# Buck_12V.net
KiCad netlist of a schematic drawn in Altium Designer
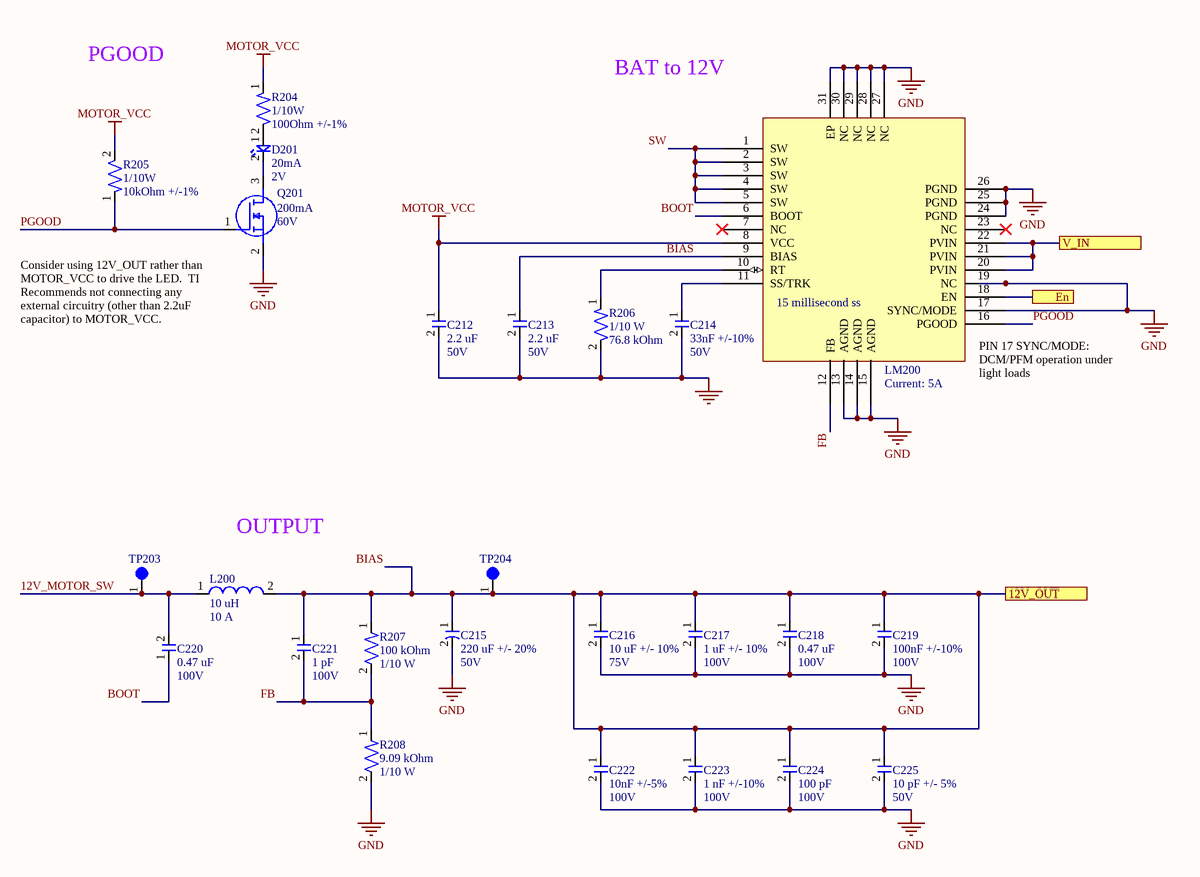
[diagram p0: Buck_12V.SchDoc]

(export (version "E")
  (design (tool "Eeschema 10.0.6"))
  (components
    (comp (ref "C212")
      (value "UMK107BBJ225KA-T")
      (footprint "CAP-0603")
      (description "2.2 µF ±10% 50V Ceramic Capacitor X5R 0603 (1608 Metric)")
      (fields (field (name "CAPACITANCE") "2.2 uF") (field (name "OLTAGE") "50V"))
      (libsource (lib "MasterLib") (part "CAP-2.2U-0001"))
    )
    (comp (ref "C213")
      (value "UMK107BBJ225KA-T")
      (footprint "CAP-0603")
      (description "2.2 µF ±10% 50V Ceramic Capacitor X5R 0603 (1608 Metric)")
      (fields (field (name "CAPACITANCE") "2.2 uF") (field (name "OLTAGE") "50V"))
      (libsource (lib "MasterLib") (part "CAP-2.2U-0001"))
    )
    (comp (ref "C214")
      (value "CC0603KRX7R9BB333")
      (footprint "CAP-0603")
      (description "0.033 µF ±10% 50V Ceramic Capacitor X7R 0603 (1608 Metric)")
      (fields
        (field (name "MANUFACTURER") "YAGEO")
        (field (name "CAPACITANCE") "33nF +/-10%")
        (field (name "VOLTAGE RATING") "50V")
      )
      (libsource (lib "MasterLib") (part "CAP-33N-0001"))
    )
    (comp (ref "C215")
      (value "50TZV220M10X10.5")
      (footprint "ELEC-220U-0003")
      (description "220 µF 50 V Aluminum Electrolytic Capacitors Radial, Can - SMD 2000 Hrs @ 105°C")
      (fields (field (name "CAPACITANCE") "220 uF +/- 20%") (field (name "VOLTAGE RATING") "50V"))
      (libsource (lib "MasterLib") (part "ELEC-220U-0003"))
    )
    (comp (ref "C216")
      (value "C3225X7R1N106K250AC")
      (footprint "CAP-1210")
      (description "10 µF ±10% 75V Ceramic Capacitor X7R 1210 (3225 Metric)")
      (fields (field (name "CAPACITANCE") "10 uF +/- 10%") (field (name "VOLTAGE RATING") "75V"))
      (libsource (lib "MasterLib") (part "CAP-10U-0004"))
    )
    (comp (ref "C217")
      (value "CL31B105KCHNNNE")
      (footprint "CAP-1206 - duplicate")
      (description "1 µF ±10% 100V Ceramic Capacitor X7R 1206 (3216 Metric)")
      (fields (field (name "CAPACITANCE") "1 uF +/- 10%") (field (name "VOLTAGE") "100V"))
      (libsource (lib "MasterLib") (part "CAP-1U-0001"))
    )
    (comp (ref "C218")
      (value "KAM21KR72A474KL")
      (footprint "CAP-0805")
      (description "0.47 µF ±10% 100V Ceramic Capacitor X7R 0805 (2012 Metric)")
      (fields
        (field (name "TOLERANCE") "+/- 10%")
        (field (name "CAPACITANCE") "0.47 uF")
        (field (name "VOLTAGE") "100V")
      )
      (libsource (lib "MasterLib") (part "CAP-0.47U-0001"))
    )
    (comp (ref "C219")
      (value "CC0603KRX7R0BB104")
      (footprint "CAP-0603")
      (description "CAP CER 0.1UF 100V X7R 0603")
      (fields
        (field (name "MANUFACTURER") "YAGEO")
        (field (name "CAPACITANCE") "100nF +/-10%")
        (field (name "VOLTAGE RATING") "100V")
      )
      (libsource (lib "MasterLib") (part "CAP-100N-0001"))
    )
    (comp (ref "C220")
      (value "KAM21KR72A474KL")
      (footprint "CAP-0805")
      (description "0.47 µF ±10% 100V Ceramic Capacitor X7R 0805 (2012 Metric)")
      (fields
        (field (name "TOLERANCE") "+/- 10%")
        (field (name "CAPACITANCE") "0.47 uF")
        (field (name "VOLTAGE") "100V")
      )
      (libsource (lib "MasterLib") (part "CAP-0.47U-0001"))
    )
    (comp (ref "C221")
      (value "885012006087")
      (footprint "CAP-0603")
      (description "1 pF ±0.25pF 100V Ceramic Capacitor C0G, NP0 0603 (1608 Metric)")
      (fields
        (field (name "TOLERANCE") "+/- 0.25 pF")
        (field (name "CAPACITANCE") "1 pF")
        (field (name "VOLTAGE") "100V")
      )
      (libsource (lib "MasterLib") (part "CAP-1P-0001"))
    )
    (comp (ref "C222")
      (value "C1608C0G2A103J080AC")
      (footprint "CAP-0603")
      (description "CAP CER 10000PF 100V C0G 0603")
      (fields
        (field (name "MANUFACTURER") "TDK Corporation")
        (field (name "CAPACITANCE") "10nF +/-5%")
        (field (name "VOLTAGE RATING") "100V")
      )
      (libsource (lib "MasterLib") (part "CAP-10N-0002"))
    )
    (comp (ref "C223")
      (value "C0603Y102K1RAC7867")
      (footprint "CAP-0603")
      (description "1000 pF ±10% 100V Ceramic Capacitor X7R 0603 (1608 Metric)")
      (fields (field (name "CAPACITANCE") "1 nF +/-10%") (field (name "VOLTAGE") "100V"))
      (libsource (lib "MasterLib") (part "CAP-1N-0001"))
    )
    (comp (ref "C224")
      (value "0603N101J101CT")
      (footprint "CAP-0603")
      (description "100 pF ±5% 100V Ceramic Capacitor C0G, NP0 0603 (1608 Metric)")
      (fields
        (field (name "TOLERANCE") "+/-5%")
        (field (name "CAPACITANCE") "100 pF")
        (field (name "VOLTAGE") "100V")
      )
      (libsource (lib "MasterLib") (part "CAP-100P-0002"))
    )
    (comp (ref "C225")
      (value "0603N100J500CT")
      (footprint "CAP-0603")
      (description "10 pF ±5% 50V Ceramic Capacitor C0G, NP0 0603 (1608 Metric)")
      (fields
        (field (name "MANUFACTURER") "Walshin Technology Corporation")
        (field (name "CAPACITANCE") "10 pF +/- 5%")
        (field (name "VOLTAGE RATING") "50V")
      )
      (libsource (lib "MasterLib") (part "CAP-10P-0001"))
    )
    (comp (ref "D201")
      (value "150060AS75000")
      (footprint "LED-0603")
      (description "CAP CER 0.1UF 100V X7R 0603")
      (fields
        (field (name "MANUFACTURER") "Wurth Electronik")
        (field (name "CURRENT RATING") "20mA")
        (field (name "VF") "2V")
      )
      (libsource (lib "MasterLib") (part "LED_Amber_0001"))
    )
    (comp (ref "L200")
      (value "SRP1270-100M")
      (footprint "PWRIND-10U-0002")
      (description "10 µH Shielded Drum Core, Wirewound Inductor 10 A 16.8mOhm Max Nonstandard")
      (fields
        (field (name "TOLERANCE") "+/- 20%")
        (field (name "INDUCTANCE") "10 uH")
        (field (name "DCI") "10 A")
      )
      (libsource (lib "MasterLib") (part "PWRIND-10U-0002"))
    )
    (comp (ref "LM200")
      (value "LM76005RNPR")
      (footprint "IC-30-WQFN(6x4)")
      (description "Buck Switching Regulator IC Positive Adjustable 1V 1 Output 5A 30-WFQFN Exposed Pad")
      (fields (field (name "MANUFACTURER") "Texas Instruments") (field (name "CURRENT") "5A"))
      (libsource (lib "MasterLib") (part "IC-BUCK-0006"))
    )
    (comp (ref "Q201")
      (value "T2N7002AK,LM")
      (footprint "NMOS-SOT23-3")
      (description "MOSFET N-CH 60V 200MA SOT23")
      (fields
        (field (name "MANUFACTURER") "Toshiba")
        (field (name "ID-CONTINUOUS") "200mA")
        (field (name "VDS-MAX") "60V")
      )
      (libsource (lib "MasterLib") (part "NMOS-200MA-0001"))
    )
    (comp (ref "R204")
      (value "AC0603FR-10100RL")
      (footprint "RES-0603")
      (description "100 Ohms ±1% 0.1W, 1/10W Chip Resistor 0603 (1608 Metric) Automotive AEC-Q200 Thick Film")
      (fields
        (field (name "MANUFACTURER") "YAGEO")
        (field (name "POWER RATING") "1/10W")
        (field (name "RESISTANCE") "100Ohm +/-1%")
      )
      (libsource (lib "MasterLib") (part "RES-100-0002"))
    )
    (comp (ref "R205")
      (value "RC0603FR-0710KP")
      (footprint "RES-0603")
      (description "RES SMD 10K OHM 1% 1/10W 0603")
      (fields
        (field (name "MANUFACTURER") "YAGEO")
        (field (name "POWER RATING") "1/10W")
        (field (name "RESISTANCE") "10kOhm +/-1%")
      )
      (libsource (lib "MasterLib") (part "RES-10K-0002"))
    )
    (comp (ref "R206")
      (value "RC0603FR-0776K8L")
      (footprint "RES-0603")
      (description "76.8 kOhms ±1% 0.1W, 1/10W Chip Resistor 0603 (1608 Metric) Moisture Resistant Thick Film")
      (fields
        (field (name "MANUFACTURER") "Yageo")
        (field (name "TOLERANCE") "+/- 1%")
        (field (name "POWER") "1/10 W")
        (field (name "RESISTANCE") "76.8 kOhm")
      )
      (libsource (lib "MasterLib") (part "RES-76.8K-0001"))
    )
    (comp (ref "R207")
      (value "RC0603FR-07100KL")
      (footprint "RES-0603")
      (description "100 kOhms ±1% 0.1W, 1/10W Chip Resistor 0603 (1608 Metric) Moisture Resistant Thick Film")
      (fields
        (field (name "TOLERANCE") "+/- 1%")
        (field (name "RESISTANCE") "100 kOhm")
        (field (name "POWER") "1/10 W")
      )
      (libsource (lib "MasterLib") (part "RES-100K-0003"))
    )
    (comp (ref "R208")
      (value "RC0603FR-079K09L")
      (footprint "RES-0603")
      (description "9.09 kOhms ±1% 0.1W, 1/10W Chip Resistor 0603 (1608 Metric) Moisture Resistant Thick Film")
      (fields
        (field (name "TOLERANCE") "+/-1%")
        (field (name "RESISTANCE") "9.09 kOhm")
        (field (name "POWER") "1/10 W")
      )
      (libsource (lib "MasterLib") (part "RES-9.09K-0001"))
    )
    (comp (ref "TP203")
      (value "5003")
      (footprint "TEST-POINT-0001")
      (description "Oranange PC Test Point, Miniature Phoisphor Bronze Silver Plating Through Hole Mounting Type")
      (libsource (lib "MasterLib") (part "TEST-POINT-0001"))
    )
    (comp (ref "TP204")
      (value "5003")
      (footprint "TEST-POINT-0001")
      (description "Oranange PC Test Point, Miniature Phoisphor Bronze Silver Plating Through Hole Mounting Type")
      (libsource (lib "MasterLib") (part "TEST-POINT-0001"))
    )
  )
  (nets
    (net (code "1") (name "/12V_MOTOR_SW") (class "Default")
      (node (ref "C220") (pin "2") (pinfunction "2_2") (pintype "passive"))
      (node (ref "L200") (pin "1") (pinfunction "1_1") (pintype "passive"))
      (node (ref "TP203") (pin "1") (pinfunction "0_1") (pintype "passive"))
    )
    (net (code "2") (name "/BIAS") (class "Default")
      (node (ref "C213") (pin "1") (pinfunction "1_1") (pintype "passive"))
      (node (ref "C215") (pin "1") (pinfunction "1_1") (pintype "passive"))
      (node (ref "C216") (pin "1") (pinfunction "1_1") (pintype "passive"))
      (node (ref "C217") (pin "1") (pinfunction "1_1") (pintype "passive"))
      (node (ref "C218") (pin "1") (pinfunction "1_1") (pintype "passive"))
      (node (ref "C219") (pin "1") (pinfunction "1_1") (pintype "passive"))
      (node (ref "C221") (pin "1") (pinfunction "1_1") (pintype "passive"))
      (node (ref "C222") (pin "1") (pinfunction "1_1") (pintype "passive"))
      (node (ref "C223") (pin "1") (pinfunction "1_1") (pintype "passive"))
      (node (ref "C224") (pin "1") (pinfunction "1_1") (pintype "passive"))
      (node (ref "C225") (pin "1") (pinfunction "1_1") (pintype "passive"))
      (node (ref "L200") (pin "2") (pinfunction "2_2") (pintype "passive"))
      (node (ref "LM200") (pin "9") (pinfunction "BIAS_9") (pintype "power_in"))
      (node (ref "R207") (pin "1") (pinfunction "1_1") (pintype "passive"))
      (node (ref "TP204") (pin "1") (pinfunction "0_1") (pintype "passive"))
    )
    (net (code "3") (name "/BOOT") (class "Default")
      (node (ref "C220") (pin "1") (pinfunction "1_1") (pintype "passive"))
      (node (ref "LM200") (pin "6") (pinfunction "BOOT_6") (pintype "power_in"))
    )
    (net (code "4") (name "/En") (class "Default")
      (node (ref "LM200") (pin "18") (pinfunction "EN_18") (pintype "power_in"))
    )
    (net (code "5") (name "/FB") (class "Default")
      (node (ref "C221") (pin "2") (pinfunction "2_2") (pintype "passive"))
      (node (ref "LM200") (pin "12") (pinfunction "FB_12") (pintype "power_in"))
      (node (ref "R207") (pin "2") (pinfunction "2_2") (pintype "passive"))
      (node (ref "R208") (pin "1") (pinfunction "1_1") (pintype "passive"))
    )
    (net (code "6") (name "/PGOOD") (class "Default")
      (node (ref "LM200") (pin "16") (pinfunction "PGOOD_16") (pintype "power_in"))
      (node (ref "Q201") (pin "1") (pinfunction "G_1") (pintype "passive"))
      (node (ref "R205") (pin "1") (pinfunction "1_1") (pintype "passive"))
    )
    (net (code "7") (name "/SW") (class "Default")
      (node (ref "LM200") (pin "1") (pinfunction "SW_1") (pintype "power_in"))
      (node (ref "LM200") (pin "2") (pinfunction "SW_2") (pintype "power_in"))
      (node (ref "LM200") (pin "3") (pinfunction "SW_3") (pintype "power_in"))
      (node (ref "LM200") (pin "4") (pinfunction "SW_4") (pintype "power_in"))
      (node (ref "LM200") (pin "5") (pinfunction "SW_5") (pintype "power_in"))
    )
    (net (code "8") (name "/V_IN") (class "Default")
      (node (ref "LM200") (pin "20") (pinfunction "PVIN_20") (pintype "power_in"))
      (node (ref "LM200") (pin "21") (pinfunction "PVIN_21") (pintype "power_in"))
      (node (ref "LM200") (pin "22") (pinfunction "PVIN_22") (pintype "power_in"))
    )
    (net (code "9") (name "<NO NET>") (class "Default")
      (node (ref "C212") (pin "2") (pinfunction "2_2") (pintype "passive"))
      (node (ref "C213") (pin "2") (pinfunction "2_2") (pintype "passive"))
      (node (ref "C214") (pin "2") (pinfunction "2_2") (pintype "passive"))
      (node (ref "R206") (pin "2") (pinfunction "2_2") (pintype "passive"))
    )
    (net (code "10") (name "GND") (class "Default")
      (node (ref "C215") (pin "2") (pinfunction "2_2") (pintype "passive"))
      (node (ref "C216") (pin "2") (pinfunction "2_2") (pintype "passive"))
      (node (ref "C217") (pin "2") (pinfunction "2_2") (pintype "passive"))
      (node (ref "C218") (pin "2") (pinfunction "2_2") (pintype "passive"))
      (node (ref "C219") (pin "2") (pinfunction "2_2") (pintype "passive"))
      (node (ref "C222") (pin "2") (pinfunction "2_2") (pintype "passive"))
      (node (ref "C223") (pin "2") (pinfunction "2_2") (pintype "passive"))
      (node (ref "C224") (pin "2") (pinfunction "2_2") (pintype "passive"))
      (node (ref "C225") (pin "2") (pinfunction "2_2") (pintype "passive"))
      (node (ref "LM200") (pin "13") (pinfunction "AGND_13") (pintype "power_in"))
      (node (ref "LM200") (pin "14") (pinfunction "AGND_14") (pintype "power_in"))
      (node (ref "LM200") (pin "15") (pinfunction "AGND_15") (pintype "power_in"))
      (node (ref "LM200") (pin "17") (pinfunction "SYNC/MODE_17") (pintype "power_in"))
      (node (ref "LM200") (pin "19") (pinfunction "NC_19") (pintype "power_in"))
      (node (ref "LM200") (pin "24") (pinfunction "PGND_24") (pintype "power_in"))
      (node (ref "LM200") (pin "25") (pinfunction "PGND_25") (pintype "power_in"))
      (node (ref "LM200") (pin "26") (pinfunction "PGND_26") (pintype "power_in"))
      (node (ref "LM200") (pin "27") (pinfunction "NC_27") (pintype "power_in"))
      (node (ref "LM200") (pin "28") (pinfunction "NC_28") (pintype "power_in"))
      (node (ref "LM200") (pin "29") (pinfunction "NC_29") (pintype "power_in"))
      (node (ref "LM200") (pin "30") (pinfunction "NC_30") (pintype "power_in"))
      (node (ref "LM200") (pin "31") (pinfunction "EP_31") (pintype "power_in"))
      (node (ref "Q201") (pin "2") (pinfunction "S_2") (pintype "passive"))
      (node (ref "R208") (pin "2") (pinfunction "2_2") (pintype "passive"))
    )
    (net (code "11") (name "MOTOR_VCC") (class "Default")
      (node (ref "C212") (pin "1") (pinfunction "1_1") (pintype "passive"))
      (node (ref "LM200") (pin "8") (pinfunction "VCC_8") (pintype "power_in"))
      (node (ref "R204") (pin "1") (pinfunction "1_1") (pintype "passive"))
      (node (ref "R205") (pin "2") (pinfunction "2_2") (pintype "passive"))
    )
    (net (code "12") (name "Net-(D201-Pad1)") (class "Default")
      (node (ref "D201") (pin "1") (pinfunction "1_1") (pintype "passive"))
      (node (ref "R204") (pin "2") (pinfunction "2_2") (pintype "passive"))
    )
    (net (code "13") (name "Net-(LM200-RT)") (class "Default")
      (node (ref "LM200") (pin "10") (pinfunction "RT_10") (pintype "bidirectional"))
      (node (ref "R206") (pin "1") (pinfunction "1_1") (pintype "passive"))
    )
    (net (code "14") (name "Net-(LM200-SS{slash}TRK)") (class "Default")
      (node (ref "C214") (pin "1") (pinfunction "1_1") (pintype "passive"))
      (node (ref "LM200") (pin "11") (pinfunction "SS/TRK_11") (pintype "passive"))
    )
    (net (code "15") (name "Net-(Q201-D)") (class "Default")
      (node (ref "D201") (pin "2") (pinfunction "2_2") (pintype "passive"))
      (node (ref "Q201") (pin "3") (pinfunction "D_3") (pintype "passive"))
    )
    (net (code "16") (name "unconnected-(LM200-NC-Pad7)") (class "Default")
      (node (ref "LM200") (pin "7") (pinfunction "NC_7") (pintype "power_in+no_connect"))
    )
    (net (code "17") (name "unconnected-(LM200-NC-Pad23)") (class "Default")
      (node (ref "LM200") (pin "23") (pinfunction "NC_23") (pintype "tri_state+no_connect"))
    )
  )
)
